# TSOC_USBUART2_test.net
KiCad netlist of a schematic drawn in EAGLE
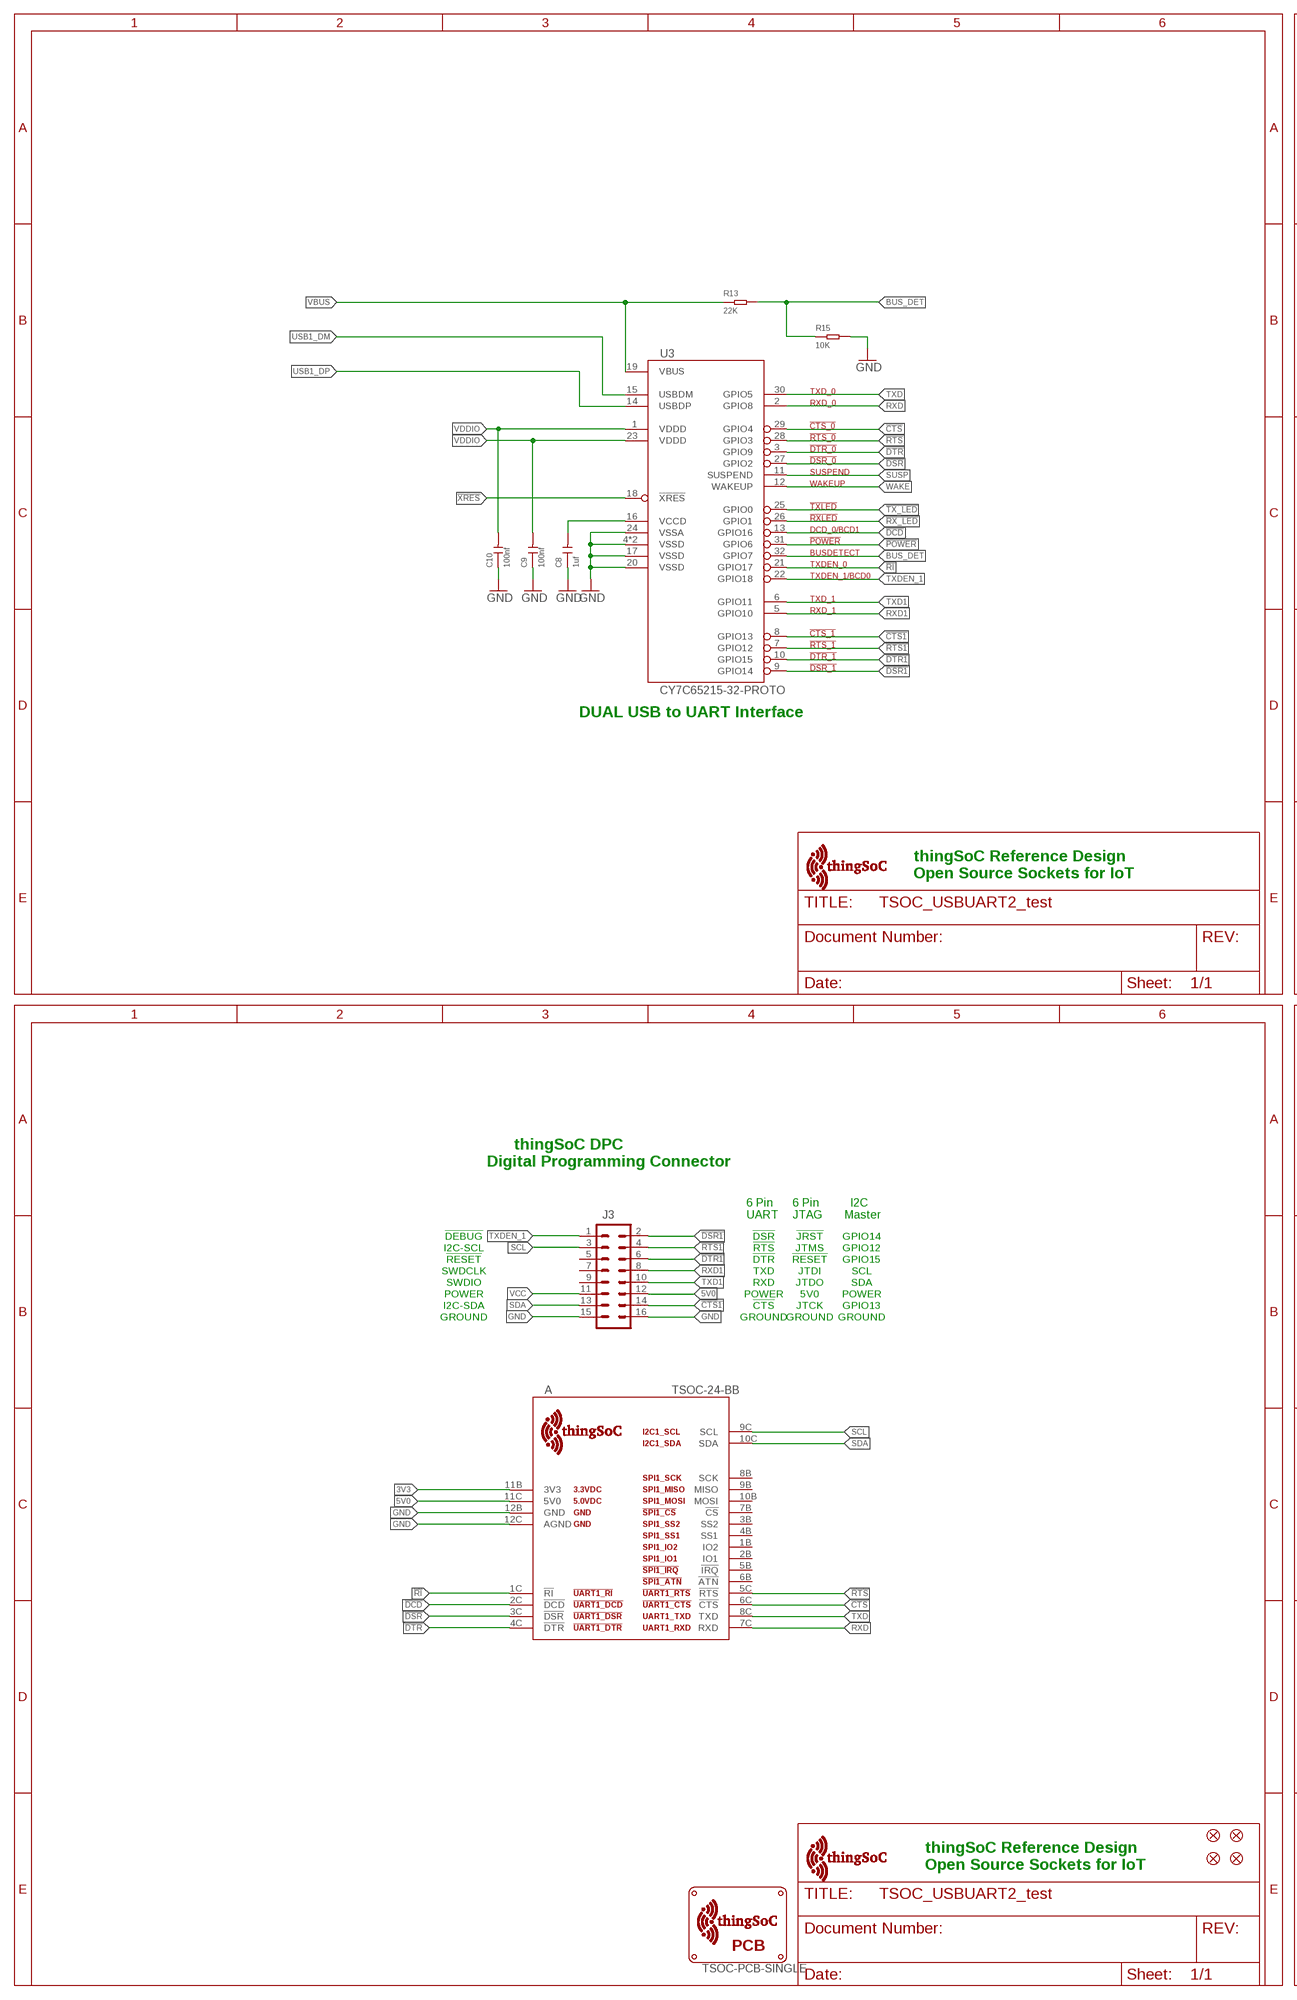
[diagram p0: schematic, sheet 1, part 1 of 2]
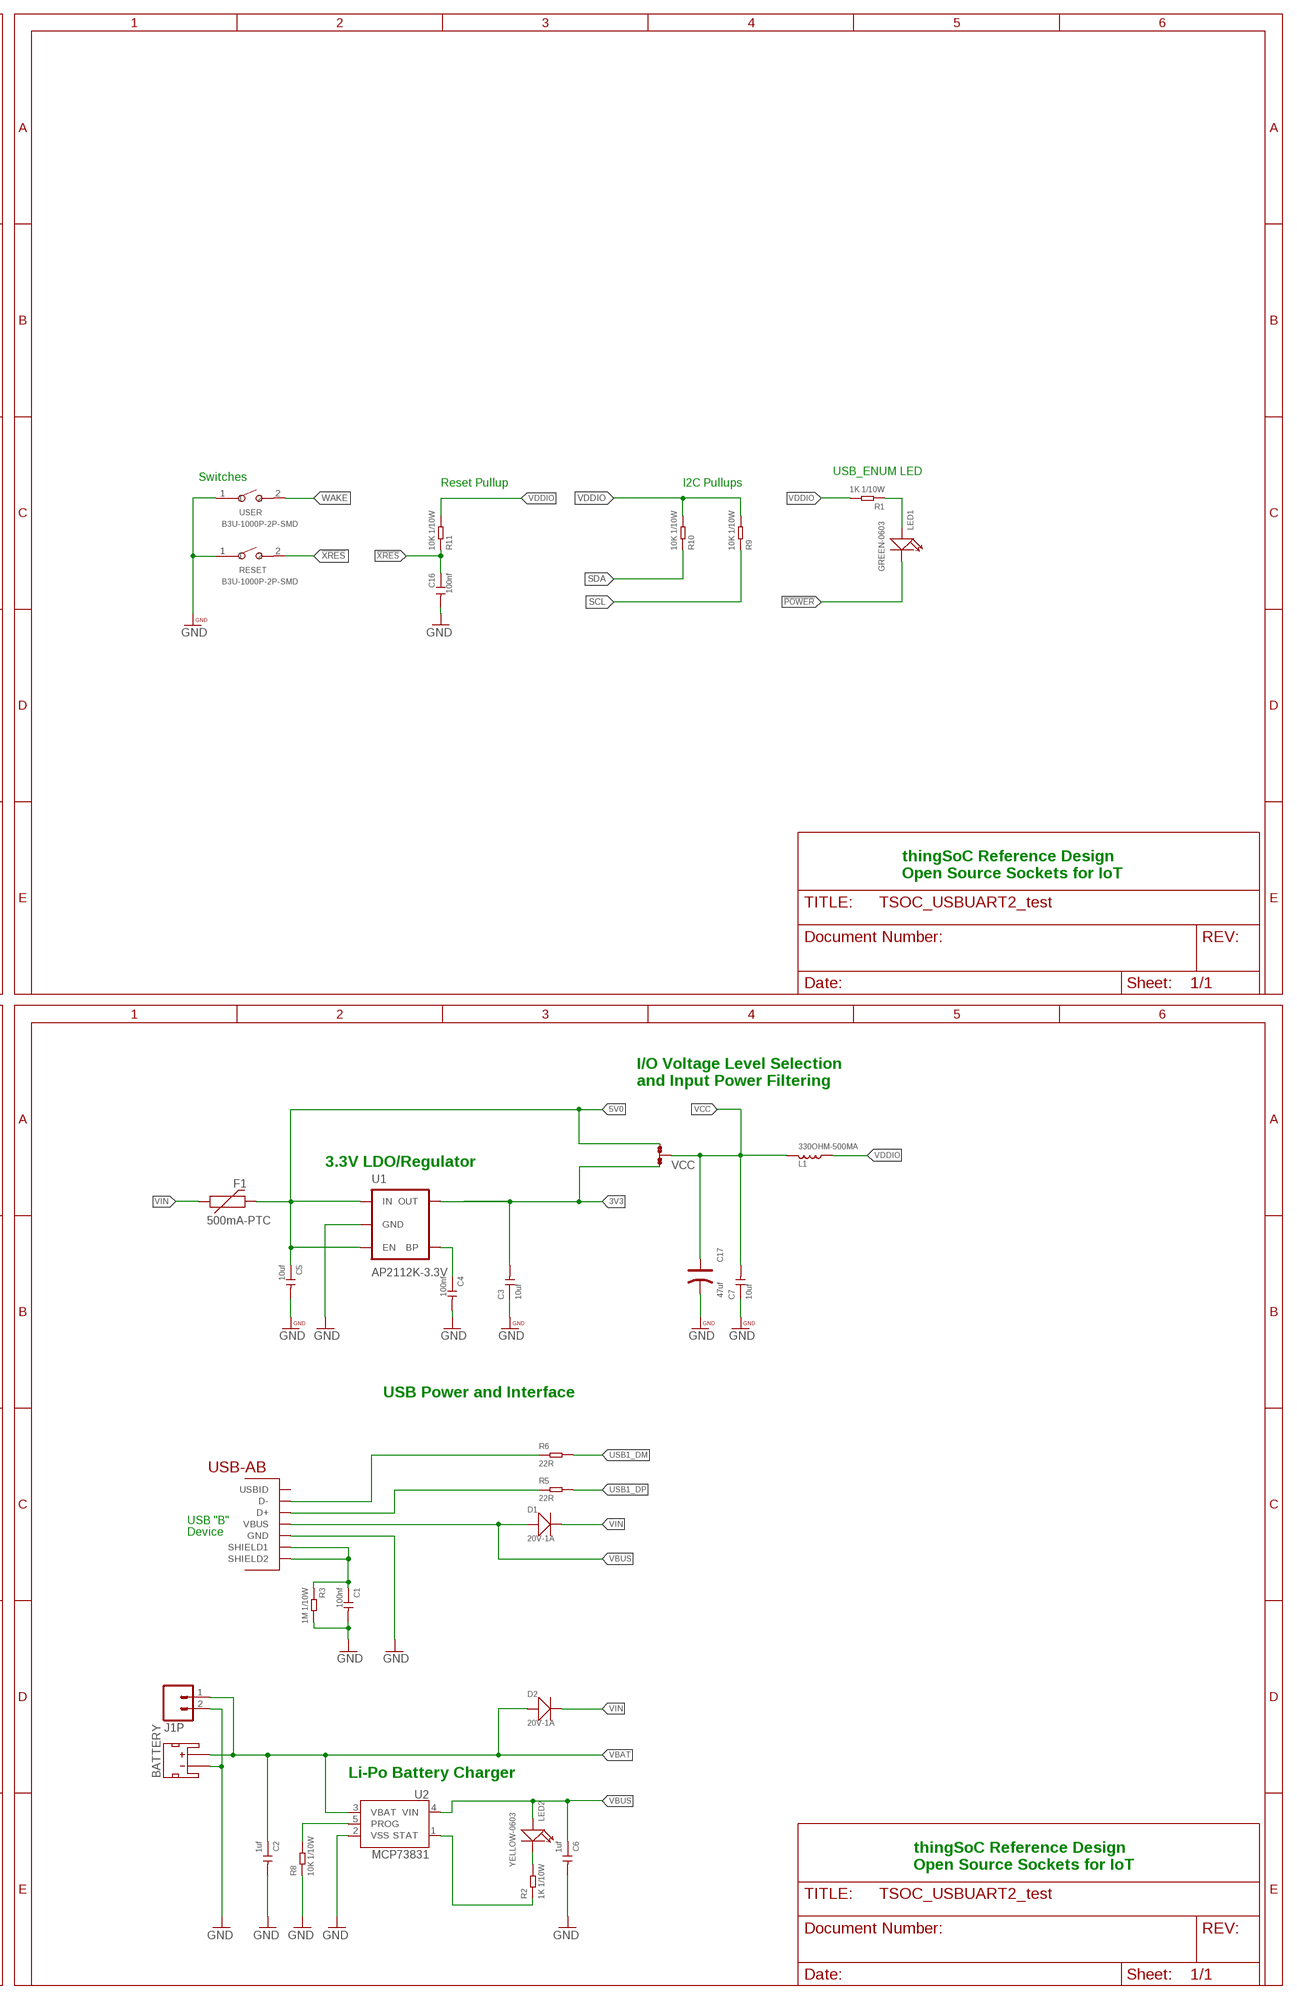
[diagram p1: schematic, sheet 1, part 2 of 2]

(export (version "E")
  (design (tool "Eeschema 10.0.6"))
  (components
    (comp (ref "A")
      (value "TSOC-24-BB")
      (footprint "eagle-import:TSOC-BB-S24")
      (libsource (lib "eagle-import") (part "TSOC-24-BB"))
    )
    (comp (ref "BATTERY")
      (value "JST_2MM_MALE")
      (footprint "eagle-import:JST-2-SMD")
      (libsource (lib "eagle-import") (part "JST_2MM_MALE"))
    )
    (comp (ref "C1")
      (value "100nf")
      (footprint "eagle-import:C0603")
      (fields (field (name "MPN") "CC0603KRX7R9BB104"))
      (libsource (lib "eagle-import") (part "CERAMIC-100NF-50V-10%-X7R(0603)"))
    )
    (comp (ref "C2")
      (value "1uf")
      (footprint "eagle-import:C0603")
      (fields (field (name "MPN") "CC0603KRX7R8BB105"))
      (libsource (lib "eagle-import") (part "CERAMIC-1UF-25V-10%-X7R(0603)"))
    )
    (comp (ref "C3")
      (value "10uf")
      (footprint "eagle-import:C0603")
      (fields (field (name "MPN") "CC0603KRX5R6BB106"))
      (libsource (lib "eagle-import") (part "CERAMIC-10UF-10V-10%-X5R(0603)"))
    )
    (comp (ref "C4")
      (value "100nf")
      (footprint "eagle-import:C0603")
      (fields (field (name "MPN") "CC0603KRX7R9BB104"))
      (libsource (lib "eagle-import") (part "CERAMIC-100NF-50V-10%-X7R(0603)"))
    )
    (comp (ref "C5")
      (value "10uf")
      (footprint "eagle-import:C0603")
      (fields (field (name "MPN") "CC0603KRX5R6BB106"))
      (libsource (lib "eagle-import") (part "CERAMIC-10UF-10V-10%-X5R(0603)"))
    )
    (comp (ref "C6")
      (value "1uf")
      (footprint "eagle-import:C0603")
      (fields (field (name "MPN") "CC0603KRX7R8BB105"))
      (libsource (lib "eagle-import") (part "CERAMIC-1UF-25V-10%-X7R(0603)"))
    )
    (comp (ref "C7")
      (value "10uf")
      (footprint "eagle-import:C0603")
      (fields (field (name "MPN") "CC0603KRX5R6BB106"))
      (libsource (lib "eagle-import") (part "CERAMIC-10UF-10V-10%-X5R(0603)"))
    )
    (comp (ref "C8")
      (value "1uf")
      (footprint "eagle-import:C0603")
      (fields (field (name "MPN") "CC0603KRX7R8BB105"))
      (libsource (lib "eagle-import") (part "CERAMIC-1UF-25V-10%-X7R(0603)"))
    )
    (comp (ref "C9")
      (value "100nf")
      (footprint "eagle-import:C0603")
      (fields (field (name "MPN") "CC0603KRX7R9BB104"))
      (libsource (lib "eagle-import") (part "CERAMIC-100NF-50V-10%-X7R(0603)"))
    )
    (comp (ref "C10")
      (value "100nf")
      (footprint "eagle-import:C0603")
      (fields (field (name "MPN") "CC0603KRX7R9BB104"))
      (libsource (lib "eagle-import") (part "CERAMIC-100NF-50V-10%-X7R(0603)"))
    )
    (comp (ref "C16")
      (value "100nf")
      (footprint "eagle-import:C0603")
      (fields (field (name "MPN") "CC0603KRX7R9BB104"))
      (libsource (lib "eagle-import") (part "CERAMIC-100NF-50V-10%-X7R(0603)"))
    )
    (comp (ref "C17")
      (value "47uf")
      (footprint "eagle-import:AVX-A")
      (fields (field (name "MPN") "TAJA476*006#NJ"))
      (libsource (lib "eagle-import") (part "TANTALUM-SMD-47UF-6.3V(AVX-A)"))
    )
    (comp (ref "D1")
      (value "20V-1A")
      (footprint "eagle-import:SOD-123")
      (fields (field (name "MPN") "B5819W"))
      (libsource (lib "eagle-import") (part "SMD-DIODE-SCHOTTKY-20V-1A(SOD-123)"))
    )
    (comp (ref "D2")
      (value "20V-1A")
      (footprint "eagle-import:SOD-123")
      (fields (field (name "MPN") "B5819W"))
      (libsource (lib "eagle-import") (part "SMD-DIODE-SCHOTTKY-20V-1A(SOD-123)"))
    )
    (comp (ref "F1")
      (value "500mA-PTC")
      (footprint "eagle-import:PTC-1206")
      (libsource (lib "eagle-import") (part "PTCSMD"))
    )
    (comp (ref "FID1")
      (value "FIDUCIALUFIDUCIAL")
      (footprint "eagle-import:MICRO-FIDUCIAL")
      (libsource (lib "eagle-import") (part "FIDUCIALUFIDUCIAL"))
    )
    (comp (ref "FID2")
      (value "FIDUCIALUFIDUCIAL")
      (footprint "eagle-import:MICRO-FIDUCIAL")
      (libsource (lib "eagle-import") (part "FIDUCIALUFIDUCIAL"))
    )
    (comp (ref "FID3")
      (value "FIDUCIALUFIDUCIAL")
      (footprint "eagle-import:MICRO-FIDUCIAL")
      (libsource (lib "eagle-import") (part "FIDUCIALUFIDUCIAL"))
    )
    (comp (ref "FID4")
      (value "FIDUCIALUFIDUCIAL")
      (footprint "eagle-import:MICRO-FIDUCIAL")
      (libsource (lib "eagle-import") (part "FIDUCIALUFIDUCIAL"))
    )
    (comp (ref "J1P")
      (value "M02-JST-2-PTH-NO_SILK")
      (footprint "eagle-import:JST-2-PTH-NS")
      (libsource (lib "eagle-import") (part "M02-JST-2-PTH-NO_SILK"))
    )
    (comp (ref "J3")
      (value "M08X2")
      (footprint "eagle-import:2X8")
      (libsource (lib "eagle-import") (part "M08X2"))
    )
    (comp (ref "L1")
      (value "330OHM-500MA")
      (footprint "eagle-import:L0603")
      (fields (field (name "MPN") "BLM18AG121SN1D"))
      (libsource (lib "eagle-import") (part "SMD-FERRITE-CHIP-120-OHM-500MA(0603)"))
    )
    (comp (ref "LED1")
      (value "GREEN-0603")
      (footprint "eagle-import:LED-0603")
      (fields (field (name "MPN") "19-217-G7C-AN1P2-3T"))
      (libsource (lib "eagle-import") (part "SMD-LED-CLEAR-GREEN(0603)"))
    )
    (comp (ref "LED2")
      (value "YELLOW-0603")
      (footprint "eagle-import:LED-0603")
      (fields (field (name "MPN") "19-217-Y5C-AM1N1VY-3T"))
      (libsource (lib "eagle-import") (part "SMD-LED-CLEAR-YELLOW(0603)"))
    )
    (comp (ref "R1")
      (value "1K 1/10W")
      (footprint "eagle-import:R0603")
      (fields (field (name "MPN") "RC0603JR-071KL"))
      (libsource (lib "eagle-import") (part "SMD-RES-1K-5%-1/10W(0603)"))
    )
    (comp (ref "R2")
      (value "1K 1/10W")
      (footprint "eagle-import:R0603")
      (fields (field (name "MPN") "RC0603JR-071KL"))
      (libsource (lib "eagle-import") (part "SMD-RES-1K-5%-1/10W(0603)"))
    )
    (comp (ref "R3")
      (value "1M 1/10W")
      (footprint "eagle-import:R0603")
      (fields (field (name "MPN") "RC0603JR-071ML"))
      (libsource (lib "eagle-import") (part "SMD-RES-1M-5%-1/10W(0603)"))
    )
    (comp (ref "R5")
      (value "22R")
      (footprint "eagle-import:R0603")
      (fields (field (name "MPN") "RC0603JR-0722RL"))
      (libsource (lib "eagle-import") (part "SMD-RES-22R-5%-1/10W(0603)"))
    )
    (comp (ref "R6")
      (value "22R")
      (footprint "eagle-import:R0603")
      (fields (field (name "MPN") "RC0603JR-0722RL"))
      (libsource (lib "eagle-import") (part "SMD-RES-22R-5%-1/10W(0603)"))
    )
    (comp (ref "R8")
      (value "10K 1/10W")
      (footprint "eagle-import:R0603")
      (fields (field (name "MPN") "RC0603JR-0710KL"))
      (libsource (lib "eagle-import") (part "SMD-RES-10K-5%-1/10W(0603)"))
    )
    (comp (ref "R9")
      (value "10K 1/10W")
      (footprint "eagle-import:R0603")
      (fields (field (name "MPN") "RC0603JR-0710KL"))
      (libsource (lib "eagle-import") (part "SMD-RES-10K-5%-1/10W(0603)"))
    )
    (comp (ref "R10")
      (value "10K 1/10W")
      (footprint "eagle-import:R0603")
      (fields (field (name "MPN") "RC0603JR-0710KL"))
      (libsource (lib "eagle-import") (part "SMD-RES-10K-5%-1/10W(0603)"))
    )
    (comp (ref "R11")
      (value "10K 1/10W")
      (footprint "eagle-import:R0603")
      (fields (field (name "MPN") "RC0603JR-0710KL"))
      (libsource (lib "eagle-import") (part "SMD-RES-10K-5%-1/10W(0603)"))
    )
    (comp (ref "R13")
      (value "22K")
      (footprint "eagle-import:R0603")
      (fields (field (name "MPN") "RC0603JR-0722KL"))
      (libsource (lib "eagle-import") (part "SMD-RES-22K-5%-1/10W(0603)"))
    )
    (comp (ref "R15")
      (value "10K")
      (footprint "eagle-import:R0603")
      (fields (field (name "MPN") "RC0603FR-0710KL"))
      (libsource (lib "eagle-import") (part "SMD-RES-10K-1%-1/10W(0603)"))
    )
    (comp (ref "RESET")
      (value "B3U-1000P-2P-SMD")
      (footprint "eagle-import:SW2-2.6-3.0X2.5X1.2+0.4MM")
      (libsource (lib "eagle-import") (part "SMD-BUTTON(2P-3.0X2.5X1.2+0.4MM)-B3U-1000P-2P-SMD"))
    )
    (comp (ref "U$1")
      (value "TSOC-PCB-SINGLE")
      (footprint "eagle-import:TSOC-BB-BRD-DIM")
      (libsource (lib "eagle-import") (part "TSOC-PCB-SINGLE"))
    )
    (comp (ref "U$100")
      (value "TSOC-LOGO-LRG")
      (footprint "eagle-import:TSOC-LOGO-LRG")
      (libsource (lib "eagle-import") (part "TSOC-LOGO-LRG"))
    )
    (comp (ref "U$101")
      (value "TSOC-LOGO-SMALL")
      (footprint "eagle-import:TSOC-LOGO-SML")
      (libsource (lib "eagle-import") (part "TSOC-LOGO-SMALL"))
    )
    (comp (ref "U1")
      (value "AP2112K-3.3V")
      (footprint "eagle-import:SOT23-5")
      (libsource (lib "eagle-import") (part "V_REG_LDOSMD"))
    )
    (comp (ref "U2")
      (value "MCP73831")
      (footprint "eagle-import:SOT23-5")
      (libsource (lib "eagle-import") (part "MCP73831"))
    )
    (comp (ref "U3")
      (value "CY7C65215-32-PROTO")
      (footprint "eagle-import:QFN32-PROTO")
      (libsource (lib "eagle-import") (part "CY7C65215-32-PROTO"))
    )
    (comp (ref "USB")
      (value "USB_AB")
      (footprint "eagle-import:USB-AB-MICRO-SMD")
      (libsource (lib "eagle-import") (part "USB_AB"))
    )
    (comp (ref "USER")
      (value "B3U-1000P-2P-SMD")
      (footprint "eagle-import:SW2-2.6-3.0X2.5X1.2+0.4MM")
      (libsource (lib "eagle-import") (part "SMD-BUTTON(2P-3.0X2.5X1.2+0.4MM)-B3U-1000P-2P-SMD"))
    )
    (comp (ref "VCC")
      (value "JMP-3-1_2")
      (footprint "eagle-import:JMP-3-1_2")
      (libsource (lib "eagle-import") (part "JMP-3-1_2"))
    )
  )
  (nets
    (net (code "1") (name "/~{CTS1}") (class "Default")
      (node (ref "J3") (pin "14") (pinfunction "14_14") (pintype "passive"))
      (node (ref "U3") (pin "8") (pinfunction "GPIO13_8") (pintype "input"))
    )
    (net (code "2") (name "/~{CTS}") (class "Default")
      (node (ref "A") (pin "6C") (pinfunction "~{CTS}_6C") (pintype "bidirectional"))
      (node (ref "U3") (pin "29") (pinfunction "GPIO4_29") (pintype "input"))
    )
    (net (code "3") (name "/~{DCD}") (class "Default")
      (node (ref "A") (pin "2C") (pinfunction "~{DCD}_2C") (pintype "bidirectional"))
      (node (ref "U3") (pin "13") (pinfunction "GPIO16_13") (pintype "output"))
    )
    (net (code "4") (name "/~{DSR1}") (class "Default")
      (node (ref "J3") (pin "2") (pinfunction "2_2") (pintype "passive"))
      (node (ref "U3") (pin "9") (pinfunction "GPIO14_9") (pintype "input"))
    )
    (net (code "5") (name "/~{DSR}") (class "Default")
      (node (ref "A") (pin "3C") (pinfunction "~{DSR}_3C") (pintype "bidirectional"))
      (node (ref "U3") (pin "27") (pinfunction "GPIO2_27") (pintype "input"))
    )
    (net (code "6") (name "/~{DTR1}") (class "Default")
      (node (ref "J3") (pin "6") (pinfunction "6_6") (pintype "passive"))
      (node (ref "U3") (pin "10") (pinfunction "GPIO15_10") (pintype "output"))
    )
    (net (code "7") (name "/~{DTR}") (class "Default")
      (node (ref "A") (pin "4C") (pinfunction "~{DTR}_4C") (pintype "bidirectional"))
      (node (ref "U3") (pin "3") (pinfunction "GPIO9_3") (pintype "output"))
    )
    (net (code "8") (name "/~{POWER}") (class "Default")
      (node (ref "LED1") (pin "-") (pinfunction "-_-") (pintype "passive"))
      (node (ref "U3") (pin "31") (pinfunction "GPIO6_31") (pintype "input"))
    )
    (net (code "9") (name "/~{RI}") (class "Default")
      (node (ref "A") (pin "1C") (pinfunction "~{RI}_1C") (pintype "bidirectional"))
      (node (ref "U3") (pin "21") (pinfunction "GPIO17_21") (pintype "input"))
    )
    (net (code "10") (name "/~{RTS1}") (class "Default")
      (node (ref "J3") (pin "4") (pinfunction "4_4") (pintype "passive"))
      (node (ref "U3") (pin "7") (pinfunction "GPIO12_7") (pintype "output"))
    )
    (net (code "11") (name "/~{RTS}") (class "Default")
      (node (ref "A") (pin "5C") (pinfunction "~{RTS}_5C") (pintype "bidirectional"))
      (node (ref "U3") (pin "28") (pinfunction "GPIO3_28") (pintype "output"))
    )
    (net (code "12") (name "/~{RX_LED}") (class "Default")
      (node (ref "U3") (pin "26") (pinfunction "GPIO1_26") (pintype "input"))
    )
    (net (code "13") (name "/~{TX_LED}") (class "Default")
      (node (ref "U3") (pin "25") (pinfunction "GPIO0_25") (pintype "input"))
    )
    (net (code "14") (name "/~{XRES}") (class "Default")
      (node (ref "C16") (pin "1") (pinfunction "1_1") (pintype "passive"))
      (node (ref "R11") (pin "1") (pinfunction "1_1") (pintype "passive"))
      (node (ref "RESET") (pin "2") (pinfunction "2_2") (pintype "bidirectional"))
      (node (ref "U3") (pin "18") (pinfunction "~{XRES}_18") (pintype "input"))
    )
    (net (code "15") (name "3V3") (class "Default")
      (node (ref "A") (pin "11B") (pinfunction "3V3_11B") (pintype "bidirectional"))
      (node (ref "C3") (pin "2") (pinfunction "2_2") (pintype "passive"))
      (node (ref "U1") (pin "5") (pinfunction "OUT_5") (pintype "passive"))
      (node (ref "VCC") (pin "1") (pinfunction "1_1") (pintype "passive"))
    )
    (net (code "16") (name "5V0") (class "Default")
      (node (ref "A") (pin "11C") (pinfunction "5V0_11C") (pintype "bidirectional"))
      (node (ref "C5") (pin "1") (pinfunction "1_1") (pintype "passive"))
      (node (ref "F1") (pin "2") (pinfunction "2_2") (pintype "bidirectional"))
      (node (ref "J3") (pin "12") (pinfunction "12_12") (pintype "passive"))
      (node (ref "U1") (pin "1") (pinfunction "IN_1") (pintype "input"))
      (node (ref "U1") (pin "3") (pinfunction "EN_3") (pintype "input"))
      (node (ref "VCC") (pin "3") (pinfunction "3_3") (pintype "passive"))
    )
    (net (code "17") (name "BUS_DET") (class "Default")
      (node (ref "R13") (pin "2") (pinfunction "2_2") (pintype "passive"))
      (node (ref "R15") (pin "1") (pinfunction "1_1") (pintype "passive"))
      (node (ref "U3") (pin "32") (pinfunction "GPIO7_32") (pintype "input"))
    )
    (net (code "18") (name "GND") (class "Default")
      (node (ref "A") (pin "12B") (pinfunction "GND_12B") (pintype "bidirectional"))
      (node (ref "A") (pin "12C") (pinfunction "AGND_12C") (pintype "bidirectional"))
      (node (ref "BATTERY") (pin "1") (pinfunction "-_1") (pintype "bidirectional"))
      (node (ref "C1") (pin "2") (pinfunction "2_2") (pintype "passive"))
      (node (ref "C10") (pin "1") (pinfunction "1_1") (pintype "passive"))
      (node (ref "C16") (pin "2") (pinfunction "2_2") (pintype "passive"))
      (node (ref "C17") (pin "-") (pinfunction "-_-") (pintype "passive"))
      (node (ref "C2") (pin "2") (pinfunction "2_2") (pintype "passive"))
      (node (ref "C3") (pin "1") (pinfunction "1_1") (pintype "passive"))
      (node (ref "C4") (pin "2") (pinfunction "2_2") (pintype "passive"))
      (node (ref "C5") (pin "2") (pinfunction "2_2") (pintype "passive"))
      (node (ref "C6") (pin "2") (pinfunction "2_2") (pintype "passive"))
      (node (ref "C7") (pin "1") (pinfunction "1_1") (pintype "passive"))
      (node (ref "C8") (pin "1") (pinfunction "1_1") (pintype "passive"))
      (node (ref "C9") (pin "1") (pinfunction "1_1") (pintype "passive"))
      (node (ref "J1P") (pin "2") (pinfunction "2_2") (pintype "passive"))
      (node (ref "J3") (pin "15") (pinfunction "15_15") (pintype "passive"))
      (node (ref "J3") (pin "16") (pinfunction "16_16") (pintype "passive"))
      (node (ref "R15") (pin "2") (pinfunction "2_2") (pintype "passive"))
      (node (ref "R3") (pin "2") (pinfunction "2_2") (pintype "passive"))
      (node (ref "R8") (pin "1") (pinfunction "1_1") (pintype "passive"))
      (node (ref "RESET") (pin "1") (pinfunction "1_1") (pintype "bidirectional"))
      (node (ref "U1") (pin "2") (pinfunction "GND_2") (pintype "input"))
      (node (ref "U2") (pin "2") (pinfunction "VSS_2") (pintype "power_in"))
      (node (ref "U3") (pin "17") (pinfunction "VSSD_17") (pintype "power_in"))
      (node (ref "U3") (pin "20") (pinfunction "VSSD_20") (pintype "power_in"))
      (node (ref "U3") (pin "24") (pinfunction "VSSA_24") (pintype "power_in"))
      (node (ref "U3") (pin "4") (pinfunction "VSSD_4") (pintype "power_in"))
      (node (ref "U3") (pin "EXP") (pinfunction "VSSD_EXP") (pintype "power_in"))
      (node (ref "USB") (pin "GND") (pinfunction "GND_GND") (pintype "bidirectional"))
      (node (ref "USER") (pin "1") (pinfunction "1_1") (pintype "bidirectional"))
    )
    (net (code "19") (name "Net-(C1-Pad1)") (class "Default")
      (node (ref "C1") (pin "1") (pinfunction "1_1") (pintype "passive"))
      (node (ref "R3") (pin "1") (pinfunction "1_1") (pintype "passive"))
      (node (ref "USB") (pin "SHIELD1") (pinfunction "SHIELD1_SHIELD1") (pintype "bidirectional"))
      (node (ref "USB") (pin "SHIELD2") (pinfunction "SHIELD2_SHIELD2") (pintype "bidirectional"))
    )
    (net (code "20") (name "Net-(LED1-Pad+)") (class "Default")
      (node (ref "LED1") (pin "+") (pinfunction "+_+") (pintype "passive"))
      (node (ref "R1") (pin "1") (pinfunction "1_1") (pintype "passive"))
    )
    (net (code "21") (name "Net-(LED2-Pad-)") (class "Default")
      (node (ref "LED2") (pin "-") (pinfunction "-_-") (pintype "passive"))
      (node (ref "R2") (pin "2") (pinfunction "2_2") (pintype "passive"))
    )
    (net (code "22") (name "Net-(R5-Pad1)") (class "Default")
      (node (ref "R5") (pin "1") (pinfunction "1_1") (pintype "passive"))
      (node (ref "USB") (pin "D+") (pinfunction "D+_D+") (pintype "bidirectional"))
    )
    (net (code "23") (name "Net-(R6-Pad1)") (class "Default")
      (node (ref "R6") (pin "1") (pinfunction "1_1") (pintype "passive"))
      (node (ref "USB") (pin "D-") (pinfunction "D-_D-") (pintype "bidirectional"))
    )
    (net (code "24") (name "Net-(U1-BP)") (class "Default")
      (node (ref "C4") (pin "1") (pinfunction "1_1") (pintype "passive"))
      (node (ref "U1") (pin "4") (pinfunction "BP_4") (pintype "input"))
    )
    (net (code "25") (name "Net-(U2-PROG)") (class "Default")
      (node (ref "R8") (pin "2") (pinfunction "2_2") (pintype "passive"))
      (node (ref "U2") (pin "5") (pinfunction "PROG_5") (pintype "input"))
    )
    (net (code "26") (name "Net-(U2-STAT)") (class "Default")
      (node (ref "R2") (pin "1") (pinfunction "1_1") (pintype "passive"))
      (node (ref "U2") (pin "1") (pinfunction "STAT_1") (pintype "output"))
    )
    (net (code "27") (name "Net-(U3-VCCD)") (class "Default")
      (node (ref "C8") (pin "2") (pinfunction "2_2") (pintype "passive"))
      (node (ref "U3") (pin "16") (pinfunction "VCCD_16") (pintype "output"))
    )
    (net (code "28") (name "RXD") (class "Default")
      (node (ref "A") (pin "7C") (pinfunction "RXD_7C") (pintype "bidirectional"))
      (node (ref "U3") (pin "2") (pinfunction "GPIO8_2") (pintype "input"))
    )
    (net (code "29") (name "RXD1") (class "Default")
      (node (ref "J3") (pin "8") (pinfunction "8_8") (pintype "passive"))
      (node (ref "U3") (pin "5") (pinfunction "GPIO10_5") (pintype "input"))
    )
    (net (code "30") (name "SCL") (class "Default")
      (node (ref "A") (pin "9C") (pinfunction "SCL_9C") (pintype "bidirectional"))
      (node (ref "J3") (pin "3") (pinfunction "3_3") (pintype "passive"))
      (node (ref "R9") (pin "1") (pinfunction "1_1") (pintype "passive"))
    )
    (net (code "31") (name "SDA") (class "Default")
      (node (ref "A") (pin "10C") (pinfunction "SDA_10C") (pintype "bidirectional"))
      (node (ref "J3") (pin "13") (pinfunction "13_13") (pintype "passive"))
      (node (ref "R10") (pin "1") (pinfunction "1_1") (pintype "passive"))
    )
    (net (code "32") (name "SUSP") (class "Default")
      (node (ref "U3") (pin "11") (pinfunction "SUSPEND_11") (pintype "input"))
    )
    (net (code "33") (name "TXD") (class "Default")
      (node (ref "A") (pin "8C") (pinfunction "TXD_8C") (pintype "bidirectional"))
      (node (ref "U3") (pin "30") (pinfunction "GPIO5_30") (pintype "output"))
    )
    (net (code "34") (name "TXD1") (class "Default")
      (node (ref "J3") (pin "10") (pinfunction "10_10") (pintype "passive"))
      (node (ref "U3") (pin "6") (pinfunction "GPIO11_6") (pintype "output"))
    )
    (net (code "35") (name "TXDEN_1") (class "Default")
      (node (ref "J3") (pin "1") (pinfunction "1_1") (pintype "passive"))
      (node (ref "U3") (pin "22") (pinfunction "GPIO18_22") (pintype "input"))
    )
    (net (code "36") (name "USB1_DM") (class "Default")
      (node (ref "R6") (pin "2") (pinfunction "2_2") (pintype "passive"))
      (node (ref "U3") (pin "15") (pinfunction "USBDM_15") (pintype "bidirectional"))
    )
    (net (code "37") (name "USB1_DP") (class "Default")
      (node (ref "R5") (pin "2") (pinfunction "2_2") (pintype "passive"))
      (node (ref "U3") (pin "14") (pinfunction "USBDP_14") (pintype "bidirectional"))
    )
    (net (code "38") (name "VBAT") (class "Default")
      (node (ref "BATTERY") (pin "2") (pinfunction "+_2") (pintype "bidirectional"))
      (node (ref "C2") (pin "1") (pinfunction "1_1") (pintype "passive"))
      (node (ref "D2") (pin "+") (pinfunction "+_+") (pintype "passive"))
      (node (ref "J1P") (pin "1") (pinfunction "1_1") (pintype "passive"))
      (node (ref "U2") (pin "3") (pinfunction "VBAT_3") (pintype "power_in"))
    )
    (net (code "39") (name "VBUS") (class "Default")
      (node (ref "C6") (pin "1") (pinfunction "1_1") (pintype "passive"))
      (node (ref "D1") (pin "+") (pinfunction "+_+") (pintype "passive"))
      (node (ref "LED2") (pin "+") (pinfunction "+_+") (pintype "passive"))
      (node (ref "R13") (pin "1") (pinfunction "1_1") (pintype "passive"))
      (node (ref "U2") (pin "4") (pinfunction "VIN_4") (pintype "power_in"))
      (node (ref "U3") (pin "19") (pinfunction "VBUS_19") (pintype "power_in"))
      (node (ref "USB") (pin "VBUS") (pinfunction "VBUS_VBUS") (pintype "bidirectional"))
    )
    (net (code "40") (name "VCC") (class "Default")
      (node (ref "C17") (pin "+") (pinfunction "+_+") (pintype "passive"))
      (node (ref "C7") (pin "2") (pinfunction "2_2") (pintype "passive"))
      (node (ref "J3") (pin "11") (pinfunction "11_11") (pintype "passive"))
      (node (ref "L1") (pin "1") (pinfunction "1_1") (pintype "passive"))
      (node (ref "VCC") (pin "2") (pinfunction "2_2") (pintype "passive"))
    )
    (net (code "41") (name "VDDIO") (class "Default")
      (node (ref "C10") (pin "2") (pinfunction "2_2") (pintype "passive"))
      (node (ref "C9") (pin "2") (pinfunction "2_2") (pintype "passive"))
      (node (ref "L1") (pin "2") (pinfunction "2_2") (pintype "passive"))
      (node (ref "R1") (pin "2") (pinfunction "2_2") (pintype "passive"))
      (node (ref "R10") (pin "2") (pinfunction "2_2") (pintype "passive"))
      (node (ref "R11") (pin "2") (pinfunction "2_2") (pintype "passive"))
      (node (ref "R9") (pin "2") (pinfunction "2_2") (pintype "passive"))
      (node (ref "U3") (pin "1") (pinfunction "VDDD_1") (pintype "power_in"))
      (node (ref "U3") (pin "23") (pinfunction "VDDD_23") (pintype "power_in"))
    )
    (net (code "42") (name "VIN") (class "Default")
      (node (ref "D1") (pin "-") (pinfunction "-_-") (pintype "passive"))
      (node (ref "D2") (pin "-") (pinfunction "-_-") (pintype "passive"))
      (node (ref "F1") (pin "1") (pinfunction "1_1") (pintype "bidirectional"))
    )
    (net (code "43") (name "WAKE") (class "Default")
      (node (ref "U3") (pin "12") (pinfunction "WAKEUP_12") (pintype "input"))
      (node (ref "USER") (pin "2") (pinfunction "2_2") (pintype "bidirectional"))
    )
    (net (code "44") (name "unconnected-(A-IO1-Pad2B)") (class "Default")
      (node (ref "A") (pin "2B") (pinfunction "IO1_2B") (pintype "bidirectional"))
    )
    (net (code "45") (name "unconnected-(A-IO2-Pad1B)") (class "Default")
      (node (ref "A") (pin "1B") (pinfunction "IO2_1B") (pintype "bidirectional"))
    )
    (net (code "46") (name "unconnected-(A-MISO-Pad9B)") (class "Default")
      (node (ref "A") (pin "9B") (pinfunction "MISO_9B") (pintype "bidirectional"))
    )
    (net (code "47") (name "unconnected-(A-MOSI-Pad10B)") (class "Default")
      (node (ref "A") (pin "10B") (pinfunction "MOSI_10B") (pintype "bidirectional"))
    )
    (net (code "48") (name "unconnected-(A-SCK-Pad8B)") (class "Default")
      (node (ref "A") (pin "8B") (pinfunction "SCK_8B") (pintype "bidirectional"))
    )
    (net (code "49") (name "unconnected-(A-SS1-Pad4B)") (class "Default")
      (node (ref "A") (pin "4B") (pinfunction "SS1_4B") (pintype "bidirectional"))
    )
    (net (code "50") (name "unconnected-(A-SS2-Pad3B)") (class "Default")
      (node (ref "A") (pin "3B") (pinfunction "SS2_3B") (pintype "bidirectional"))
    )
    (net (code "51") (name "unconnected-(A-~{ATN}-Pad6B)") (class "Default")
      (node (ref "A") (pin "6B") (pinfunction "~{ATN}_6B") (pintype "bidirectional"))
    )
    (net (code "52") (name "unconnected-(A-~{CS}-Pad7B)") (class "Default")
      (node (ref "A") (pin "7B") (pinfunction "~{CS}_7B") (pintype "bidirectional"))
    )
    (net (code "53") (name "unconnected-(A-~{IRQ}-Pad5B)") (class "Default")
      (node (ref "A") (pin "5B") (pinfunction "~{IRQ}_5B") (pintype "bidirectional"))
    )
    (net (code "54") (name "unconnected-(BATTERY-PAD1-PadNC1)") (class "Default")
      (node (ref "BATTERY") (pin "NC1") (pinfunction "PAD1_NC1") (pintype "bidirectional"))
    )
    (net (code "55") (name "unconnected-(BATTERY-PAD2-PadNC2)") (class "Default")
      (node (ref "BATTERY") (pin "NC2") (pinfunction "PAD2_NC2") (pintype "bidirectional"))
    )
    (net (code "56") (name "unconnected-(J3-Pad5)") (class "Default")
      (node (ref "J3") (pin "5") (pinfunction "5_5") (pintype "passive"))
    )
    (net (code "57") (name "unconnected-(J3-Pad7)") (class "Default")
      (node (ref "J3") (pin "7") (pinfunction "7_7") (pintype "passive"))
    )
    (net (code "58") (name "unconnected-(J3-Pad9)") (class "Default")
      (node (ref "J3") (pin "9") (pinfunction "9_9") (pintype "passive"))
    )
    (net (code "59") (name "unconnected-(USB-USBID-PadID)") (class "Default")
      (node (ref "USB") (pin "ID") (pinfunction "USBID_ID") (pintype "bidirectional"))
    )
  )
)
